# FIT_TCM_Main_PLL.net
KiCad netlist of a schematic drawn in Altium Designer
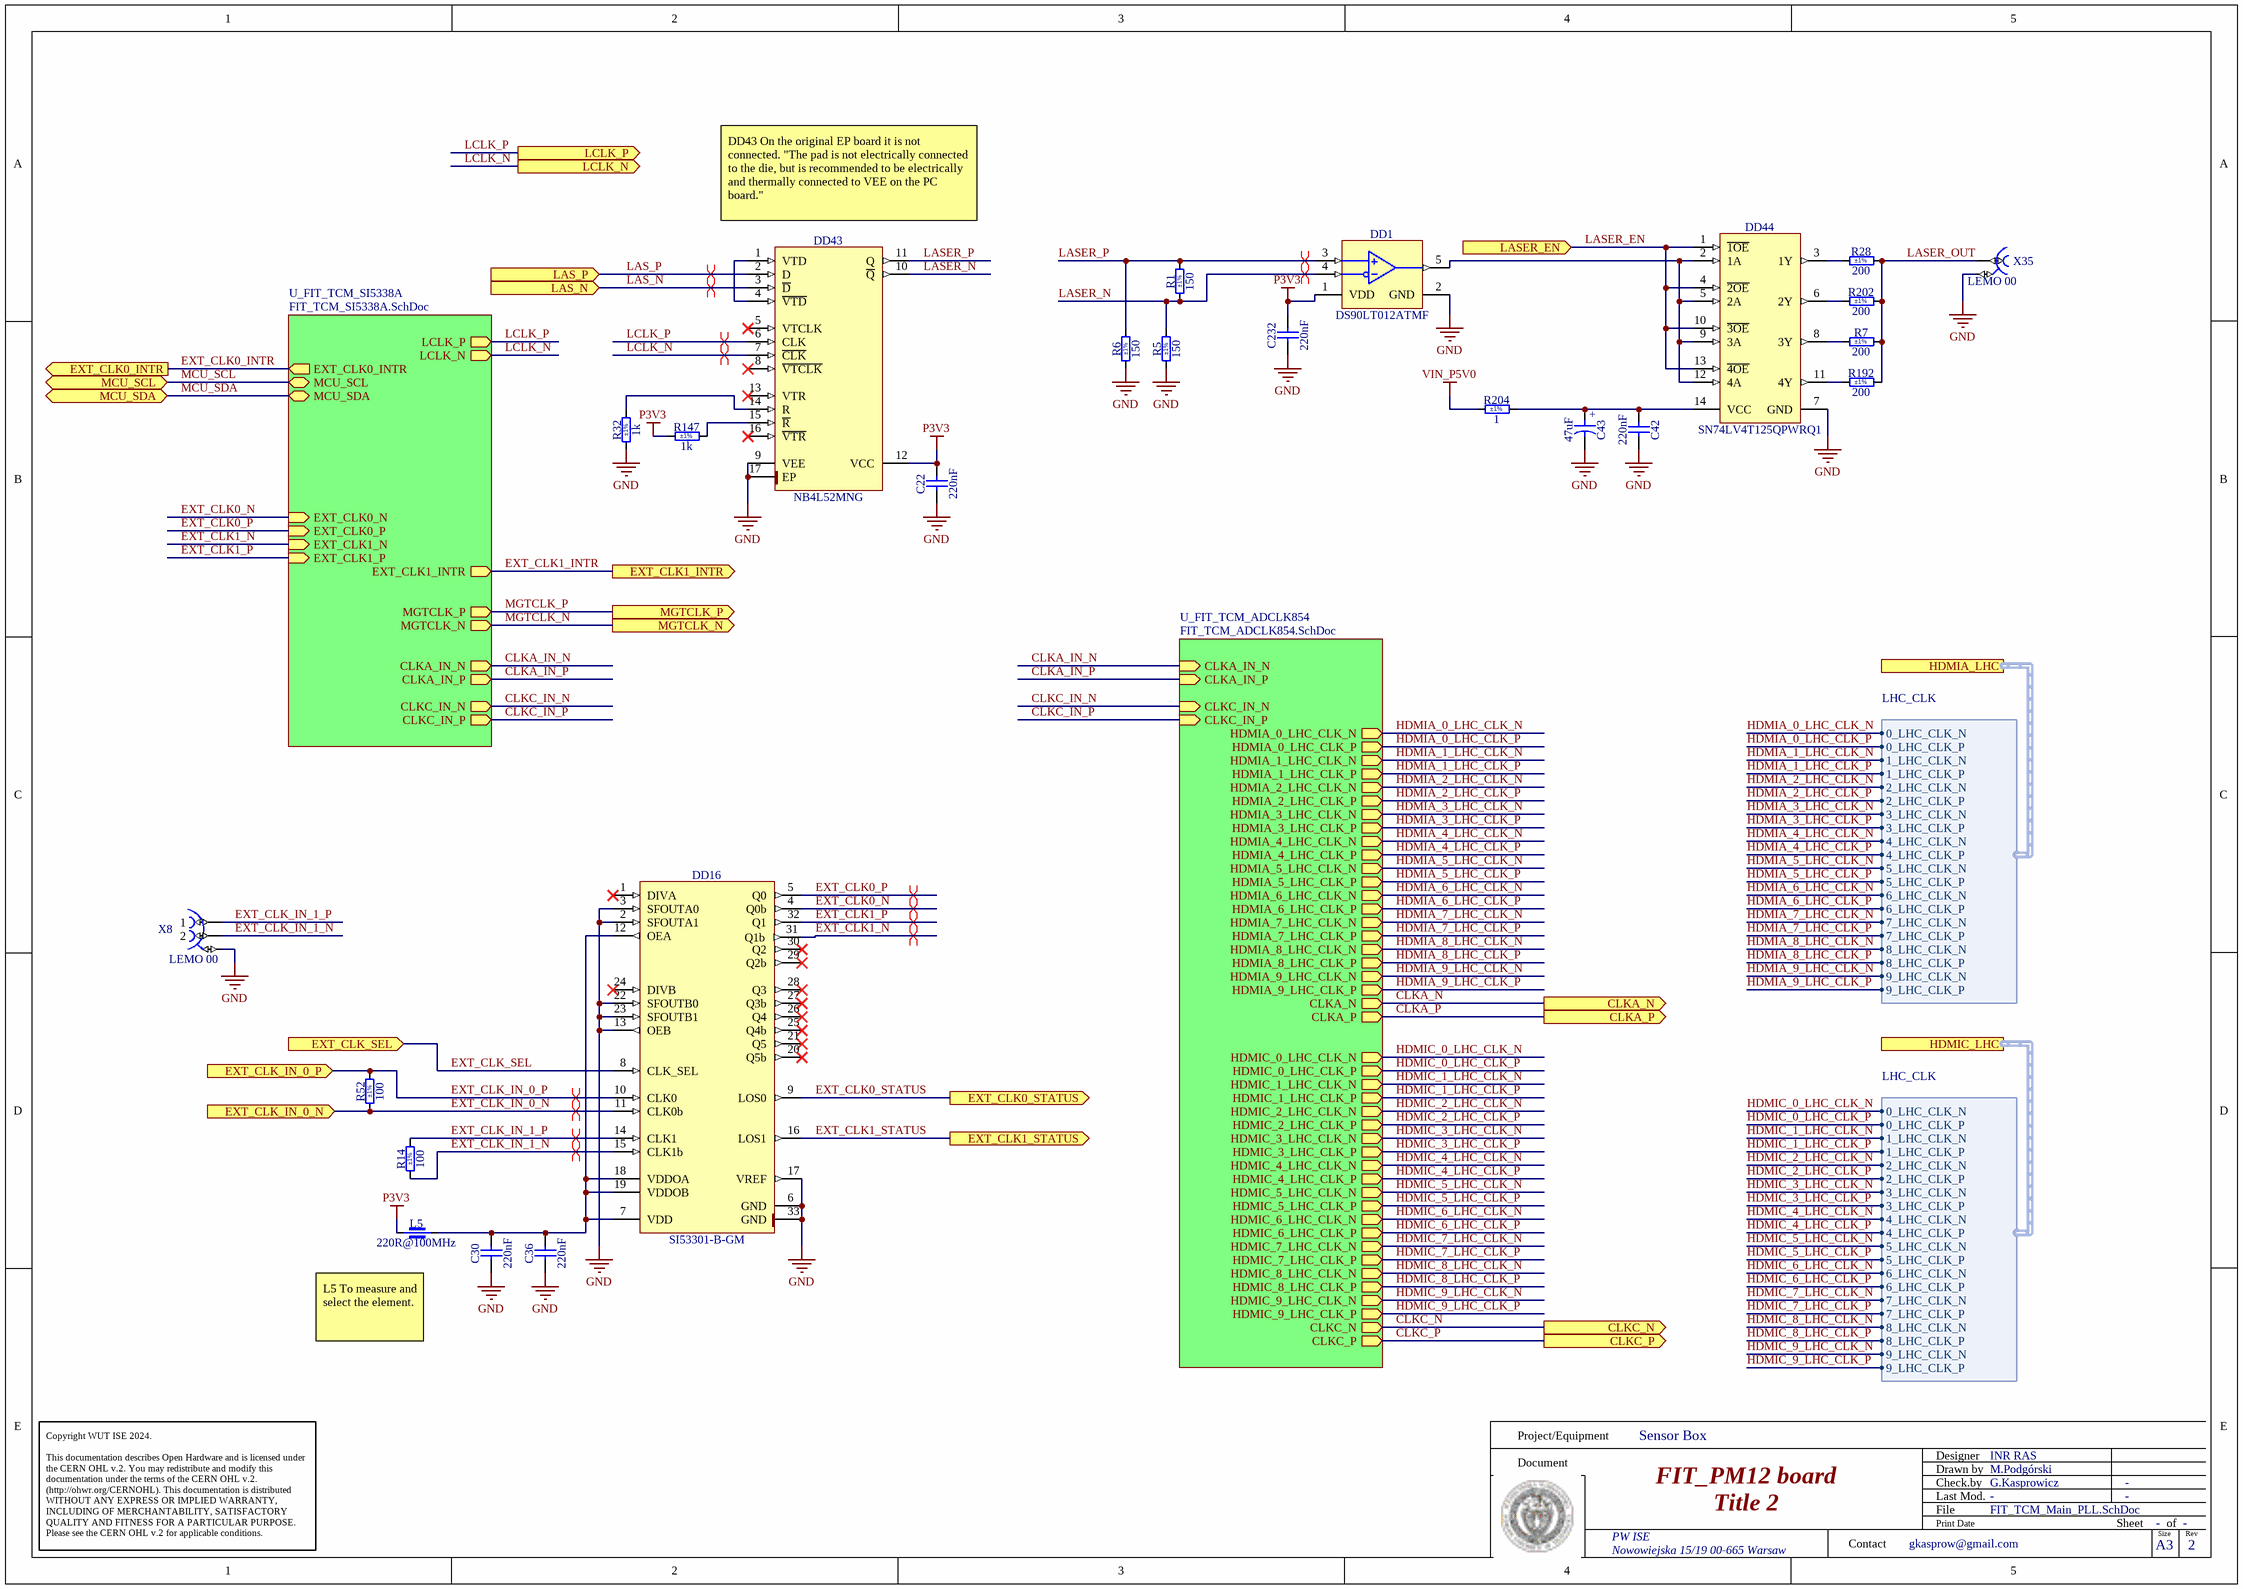
[diagram p0: FIT_TCM_Main_PLL.SchDoc]

(export (version "E")
  (design (tool "Eeschema 10.0.6"))
  (components
    (comp (ref "C22")
      (value "220nF")
      (footprint "CAPC2012X135N")
      (description "Non-polarised capacitor")
      (fields
        (field (name "PART NUMBER") "CC0805_220NF_50V_10%_X7R")
        (field (name "VOLTAGE") "50V")
        (field (name "AUTHOR") "CERN DEM JLC")
      )
      (libsource (lib "Capacitors") (part "Capacitor - non polarized"))
    )
    (comp (ref "C30")
      (value "220nF")
      (footprint "CAPC2012X135N")
      (description "Non-polarised capacitor")
      (fields
        (field (name "PART NUMBER") "CC0805_220NF_50V_10%_X7R")
        (field (name "VOLTAGE") "50V")
        (field (name "AUTHOR") "CERN DEM JLC")
      )
      (libsource (lib "Capacitors") (part "Capacitor - non polarized"))
    )
    (comp (ref "C36")
      (value "220nF")
      (footprint "CAPC2012X135N")
      (description "Non-polarised capacitor")
      (fields
        (field (name "PART NUMBER") "CC0805_220NF_50V_10%_X7R")
        (field (name "VOLTAGE") "50V")
        (field (name "AUTHOR") "CERN DEM JLC")
      )
      (libsource (lib "Capacitors") (part "Capacitor - non polarized"))
    )
    (comp (ref "C42")
      (value "220nF")
      (footprint "CAPC2012X135N")
      (description "Non-polarised capacitor")
      (fields
        (field (name "PART NUMBER") "CC0805_220NF_50V_10%_X7R")
        (field (name "VOLTAGE") "50V")
        (field (name "AUTHOR") "CERN DEM JLC")
      )
      (libsource (lib "Capacitors") (part "Capacitor - non polarized"))
    )
    (comp (ref "C43")
      (value "47uF")
      (footprint "CAPAE530X610N")
      (description "Polarised capacitor")
      (fields
        (field (name "PART NUMBER") "CAE530-610_47UF_16V_20%")
        (field (name "VOLTAGE") "16V")
        (field (name "AUTHOR") "CERN DEM HF")
      )
      (libsource (lib "Capacitors") (part "Capacitor - polarized"))
    )
    (comp (ref "C232")
      (value "220nF")
      (footprint "CAPC2012X135N")
      (description "Non-polarised capacitor")
      (fields
        (field (name "PART NUMBER") "CC0805_220NF_50V_10%_X7R")
        (field (name "VOLTAGE") "50V")
        (field (name "AUTHOR") "CERN DEM JLC")
      )
      (libsource (lib "Capacitors") (part "Capacitor - non polarized"))
    )
    (comp (ref "DD1")
      (value "DS90LT012ATMF")
      (footprint "SOT95P280X145-5N")
      (description "3V LVDS Single CMOS Differential Line Receiver")
      (fields (field (name "MANUFACTURER") "TEXAS INSTRUMENTS") (field (name "AUTHOR") "CERN DEM HF"))
      (libsource (lib "ICs And Semiconductors") (part "DS90LT012A"))
    )
    (comp (ref "DD16")
      (value "SI53301-B-GM")
      (footprint "QFN50P500X500X100-33N-S230")
      (description "I2C-Programmable Any-Frequency, Any-Output Quad Clock Generator")
      (fields (field (name "MANUFACTURER") "SKYWORKS") (field (name "AUTHOR") "CERN DEM HF"))
      (libsource (lib "ICs And Semiconductors") (part "SI53301"))
    )
    (comp (ref "DD43")
      (value "NB4L52MNG")
      (footprint "QFN50P300X300X100-17N-S185")
      (description "2.5 V/3.3 V/5.0 V Differential Data/Clock D Flip-Flop with Reset")
      (fields
        (field (name "MANUFACTURER") "ON SEMICONDUCTOR")
        (field (name "MANUFACTURER PART NUMBER") "NB4L52MN")
        (field (name "AUTHOR") "CERN DEM MR")
      )
      (libsource (lib "ICs And Semiconductors") (part "NB4L52MN"))
    )
    (comp (ref "DD44")
      (value "SN74LV4T125QPWRQ1")
      (footprint "SOP65P640X120-14N")
      (description "Quadruple Buffer Translator With 3-State Outputs")
      (fields (field (name "MANUFACTURER") "TEXAS INSTRUMENTS") (field (name "AUTHOR") "CERN DEM HF"))
      (libsource (lib "ICs And Semiconductors") (part "744T125"))
    )
    (comp (ref "L5")
      (value "220R@100MHz")
      (footprint "INDC2012X105N")
      (fields
        (field (name "PART NUMBER") "IND0805_TDK_MPZ2012S221A")
        (field (name "POWER") "3A")
        (field (name "TOLERANCE") "±25%")
        (field (name "AUTHOR") "CERN DEM HF")
      )
      (libsource (lib "Inductors & Transformers") (part "Ferrite Bead"))
    )
    (comp (ref "R1")
      (value "150")
      (footprint "RESC2012X60N")
      (description "Resistor - 1%")
      (fields
        (field (name "TOLERANCE") "±1%")
        (field (name "PART NUMBER") "R0805_150R_1%_0.125W_100PPM")
        (field (name "POWER") "0.125W")
        (field (name "AUTHOR") "CERN DEM JLC")
      )
      (libsource (lib "Resistors") (part "Resistor - 1%"))
    )
    (comp (ref "R5")
      (value "150")
      (footprint "RESC2012X60N")
      (description "Resistor - 1%")
      (fields
        (field (name "TOLERANCE") "±1%")
        (field (name "PART NUMBER") "R0805_150R_1%_0.125W_100PPM")
        (field (name "POWER") "0.125W")
        (field (name "AUTHOR") "CERN DEM JLC")
      )
      (libsource (lib "Resistors") (part "Resistor - 1%"))
    )
    (comp (ref "R6")
      (value "150")
      (footprint "RESC2012X60N")
      (description "Resistor - 1%")
      (fields
        (field (name "TOLERANCE") "±1%")
        (field (name "PART NUMBER") "R0805_150R_1%_0.125W_100PPM")
        (field (name "POWER") "0.125W")
        (field (name "AUTHOR") "CERN DEM JLC")
      )
      (libsource (lib "Resistors") (part "Resistor - 1%"))
    )
    (comp (ref "R7")
      (value "200")
      (footprint "RESC2012X60N")
      (description "Resistor - 1%")
      (fields
        (field (name "TOLERANCE") "±1%")
        (field (name "PART NUMBER") "R0805_200R_1%_0.125W_100PPM")
        (field (name "POWER") "0.125W")
        (field (name "AUTHOR") "CERN DEM JLC")
      )
      (libsource (lib "Resistors") (part "Resistor - 1%"))
    )
    (comp (ref "R14")
      (value "100")
      (footprint "RESC1608X55N")
      (description "Resistor - 1%")
      (fields
        (field (name "TOLERANCE") "±1%")
        (field (name "PART NUMBER") "R0603_100R_1%_0.1W_100PPM")
        (field (name "POWER") "0.1W")
        (field (name "AUTHOR") "CERN DEM JLC")
      )
      (libsource (lib "Resistors") (part "Resistor - 1%"))
    )
    (comp (ref "R28")
      (value "200")
      (footprint "RESC2012X60N")
      (description "Resistor - 1%")
      (fields
        (field (name "TOLERANCE") "±1%")
        (field (name "PART NUMBER") "R0805_200R_1%_0.125W_100PPM")
        (field (name "POWER") "0.125W")
        (field (name "AUTHOR") "CERN DEM JLC")
      )
      (libsource (lib "Resistors") (part "Resistor - 1%"))
    )
    (comp (ref "R32")
      (value "1k")
      (footprint "RESC2012X60N")
      (description "Resistor - 1%")
      (fields
        (field (name "TOLERANCE") "±1%")
        (field (name "PART NUMBER") "R0805_1K_1%_0.125W_100PPM")
        (field (name "POWER") "0.125W")
        (field (name "AUTHOR") "CERN DEM JLC")
      )
      (libsource (lib "Resistors") (part "Resistor - 1%"))
    )
    (comp (ref "R52")
      (value "100")
      (footprint "RESC1608X55N")
      (description "Resistor - 1%")
      (fields
        (field (name "TOLERANCE") "±1%")
        (field (name "PART NUMBER") "R0603_100R_1%_0.1W_100PPM")
        (field (name "POWER") "0.1W")
        (field (name "AUTHOR") "CERN DEM JLC")
      )
      (libsource (lib "Resistors") (part "Resistor - 1%"))
    )
    (comp (ref "R147")
      (value "1k")
      (footprint "RESC2012X60N")
      (description "Resistor - 1%")
      (fields
        (field (name "TOLERANCE") "±1%")
        (field (name "PART NUMBER") "R0805_1K_1%_0.125W_100PPM")
        (field (name "POWER") "0.125W")
        (field (name "AUTHOR") "CERN DEM JLC")
      )
      (libsource (lib "Resistors") (part "Resistor - 1%"))
    )
    (comp (ref "R192")
      (value "200")
      (footprint "RESC2012X60N")
      (description "Resistor - 1%")
      (fields
        (field (name "TOLERANCE") "±1%")
        (field (name "PART NUMBER") "R0805_200R_1%_0.125W_100PPM")
        (field (name "POWER") "0.125W")
        (field (name "AUTHOR") "CERN DEM JLC")
      )
      (libsource (lib "Resistors") (part "Resistor - 1%"))
    )
    (comp (ref "R202")
      (value "200")
      (footprint "RESC2012X60N")
      (description "Resistor - 1%")
      (fields
        (field (name "TOLERANCE") "±1%")
        (field (name "PART NUMBER") "R0805_200R_1%_0.125W_100PPM")
        (field (name "POWER") "0.125W")
        (field (name "AUTHOR") "CERN DEM JLC")
      )
      (libsource (lib "Resistors") (part "Resistor - 1%"))
    )
    (comp (ref "R204")
      (value "1")
      (footprint "RESC2012X60N")
      (description "Resistor - 1%")
      (fields
        (field (name "TOLERANCE") "±1%")
        (field (name "PART NUMBER") "R0805_1R_1%_0.125W_100PPM")
        (field (name "POWER") "0.125W")
        (field (name "AUTHOR") "CERN DEM HF")
      )
      (libsource (lib "Resistors") (part "Resistor - 1%"))
    )
    (comp (ref "X8")
      (value "LEMO 00")
      (footprint "LEMO_EPG.00.302.NLN")
      (fields
        (field (name "PART NUMBER") "LEMO_EPG.00.302.NLN")
        (field (name "MANUFACTURER") "LEMO")
        (field (name "MANUFACTURER PART NUMBER") "EPG.00.302.NLN")
        (field (name "AUTHOR") "CERN DEM JLC")
      )
      (libsource (lib "Connectors") (part "Coax_2Female_1Shield"))
    )
    (comp (ref "X35")
      (value "LEMO 00")
      (footprint "LEMO_EPL.00.250.NTN")
      (fields
        (field (name "PART NUMBER") "LEMO_EPL.00.250.NTN")
        (field (name "MANUFACTURER") "LEMO")
        (field (name "MANUFACTURER PART NUMBER") "EPL.00.250.NTN")
        (field (name "AUTHOR") "CERN DEM JLC")
      )
      (libsource (lib "Connectors") (part "Coax_1Female_1Shield"))
    )
  )
  (nets
    (net (code "11") (name "/EXT_CLK0_N") (class "Default")
      (node (ref "DD16") (pin "4") (pinfunction "Q0b_4") (pintype "output"))
    )
    (net (code "12") (name "/EXT_CLK0_P") (class "Default")
      (node (ref "DD16") (pin "5") (pinfunction "Q0_5") (pintype "output"))
    )
    (net (code "13") (name "/EXT_CLK0_STATUS") (class "Default")
      (node (ref "DD16") (pin "9") (pinfunction "LOS0_9") (pintype "output"))
    )
    (net (code "15") (name "/EXT_CLK1_N") (class "Default")
      (node (ref "DD16") (pin "31") (pinfunction "Q1b_31") (pintype "output"))
    )
    (net (code "16") (name "/EXT_CLK1_P") (class "Default")
      (node (ref "DD16") (pin "32") (pinfunction "Q1_32") (pintype "output"))
    )
    (net (code "17") (name "/EXT_CLK1_STATUS") (class "Default")
      (node (ref "DD16") (pin "16") (pinfunction "LOS1_16") (pintype "output"))
    )
    (net (code "18") (name "/EXT_CLK_IN_0_N") (class "Default")
      (node (ref "DD16") (pin "11") (pinfunction "CLK0b_11") (pintype "input"))
      (node (ref "R52") (pin "1") (pinfunction "1_1") (pintype "passive"))
    )
    (net (code "19") (name "/EXT_CLK_IN_0_P") (class "Default")
      (node (ref "DD16") (pin "10") (pinfunction "CLK0_10") (pintype "input"))
      (node (ref "R52") (pin "2") (pinfunction "2_2") (pintype "passive"))
    )
    (net (code "20") (name "/EXT_CLK_IN_1_N") (class "Default")
      (node (ref "DD16") (pin "15") (pinfunction "CLK1b_15") (pintype "input"))
      (node (ref "R14") (pin "1") (pinfunction "1_1") (pintype "passive"))
      (node (ref "X8") (pin "2") (pinfunction "2_2") (pintype "bidirectional"))
    )
    (net (code "21") (name "/EXT_CLK_IN_1_P") (class "Default")
      (node (ref "DD16") (pin "14") (pinfunction "CLK1_14") (pintype "input"))
      (node (ref "R14") (pin "2") (pinfunction "2_2") (pintype "passive"))
      (node (ref "X8") (pin "1") (pinfunction "1_1") (pintype "bidirectional"))
    )
    (net (code "22") (name "/EXT_CLK_SEL") (class "Default")
      (node (ref "DD16") (pin "8") (pinfunction "CLK_SEL_8") (pintype "input"))
    )
    (net (code "63") (name "/LASER_EN") (class "Default")
      (node (ref "DD44") (pin "1") (pinfunction "~{1OE}_1") (pintype "input"))
      (node (ref "DD44") (pin "10") (pinfunction "~{3OE}_10") (pintype "input"))
      (node (ref "DD44") (pin "13") (pinfunction "~{4OE}_13") (pintype "input"))
      (node (ref "DD44") (pin "4") (pinfunction "~{2OE}_4") (pintype "input"))
    )
    (net (code "64") (name "/LASER_N") (class "Default")
      (node (ref "DD1") (pin "4") (pinfunction "IN-_4") (pintype "input"))
      (node (ref "DD43") (pin "10") (pinfunction "~{Q}_10") (pintype "output"))
      (node (ref "R1") (pin "1") (pinfunction "1_1") (pintype "passive"))
      (node (ref "R5") (pin "2") (pinfunction "2_2") (pintype "passive"))
    )
    (net (code "65") (name "/LASER_OUT") (class "Default")
      (node (ref "R192") (pin "2") (pinfunction "2_2") (pintype "passive"))
      (node (ref "R202") (pin "2") (pinfunction "2_2") (pintype "passive"))
      (node (ref "R28") (pin "2") (pinfunction "2_2") (pintype "passive"))
      (node (ref "R7") (pin "2") (pinfunction "2_2") (pintype "passive"))
      (node (ref "X35") (pin "1") (pinfunction "1_1") (pintype "bidirectional"))
    )
    (net (code "66") (name "/LASER_P") (class "Default")
      (node (ref "DD1") (pin "3") (pinfunction "IN+_3") (pintype "input"))
      (node (ref "DD43") (pin "11") (pinfunction "Q_11") (pintype "output"))
      (node (ref "R1") (pin "2") (pinfunction "2_2") (pintype "passive"))
      (node (ref "R6") (pin "2") (pinfunction "2_2") (pintype "passive"))
    )
    (net (code "67") (name "/LAS_N") (class "Default")
      (node (ref "DD43") (pin "3") (pinfunction "~{D}_3") (pintype "input"))
    )
    (net (code "68") (name "/LAS_P") (class "Default")
      (node (ref "DD43") (pin "2") (pinfunction "D_2") (pintype "input"))
    )
    (net (code "69") (name "/LCLK_N") (class "Default")
      (node (ref "DD43") (pin "7") (pinfunction "~{CLK}_7") (pintype "input"))
    )
    (net (code "70") (name "/LCLK_P") (class "Default")
      (node (ref "DD43") (pin "6") (pinfunction "CLK_6") (pintype "input"))
    )
    (net (code "76") (name "GND") (class "Default")
      (node (ref "C22") (pin "1") (pinfunction "1_1") (pintype "passive"))
      (node (ref "C232") (pin "1") (pinfunction "1_1") (pintype "passive"))
      (node (ref "C30") (pin "1") (pinfunction "1_1") (pintype "passive"))
      (node (ref "C36") (pin "1") (pinfunction "1_1") (pintype "passive"))
      (node (ref "C42") (pin "2") (pinfunction "2_2") (pintype "passive"))
      (node (ref "C43") (pin "2") (pinfunction "2_2") (pintype "passive"))
      (node (ref "DD1") (pin "2") (pinfunction "GND_2") (pintype "power_in"))
      (node (ref "DD16") (pin "13") (pinfunction "OEB_13") (pintype "output"))
      (node (ref "DD16") (pin "17") (pinfunction "VREF_17") (pintype "output"))
      (node (ref "DD16") (pin "2") (pinfunction "SFOUTA1_2") (pintype "input"))
      (node (ref "DD16") (pin "22") (pinfunction "SFOUTB0_22") (pintype "input"))
      (node (ref "DD16") (pin "23") (pinfunction "SFOUTB1_23") (pintype "input"))
      (node (ref "DD16") (pin "3") (pinfunction "SFOUTA0_3") (pintype "input"))
      (node (ref "DD16") (pin "33") (pinfunction "GND_33") (pintype "power_in"))
      (node (ref "DD16") (pin "6") (pinfunction "GND_6") (pintype "power_in"))
      (node (ref "DD43") (pin "17") (pinfunction "EP_17") (pintype "power_in"))
      (node (ref "DD43") (pin "9") (pinfunction "VEE_9") (pintype "power_in"))
      (node (ref "DD44") (pin "7") (pinfunction "GND_7") (pintype "power_in"))
      (node (ref "R32") (pin "1") (pinfunction "1_1") (pintype "passive"))
      (node (ref "R5") (pin "1") (pinfunction "1_1") (pintype "passive"))
      (node (ref "R6") (pin "1") (pinfunction "1_1") (pintype "passive"))
      (node (ref "X35") (pin "2") (pinfunction "2_2") (pintype "bidirectional"))
      (node (ref "X8") (pin "3") (pinfunction "3_3") (pintype "bidirectional"))
    )
    (net (code "77") (name "Net-(DD1-TTLOUT)") (class "Default")
      (node (ref "DD1") (pin "5") (pinfunction "TTLOUT_5") (pintype "output"))
      (node (ref "DD44") (pin "12") (pinfunction "4A_12") (pintype "input"))
      (node (ref "DD44") (pin "2") (pinfunction "1A_2") (pintype "input"))
      (node (ref "DD44") (pin "5") (pinfunction "2A_5") (pintype "input"))
      (node (ref "DD44") (pin "9") (pinfunction "3A_9") (pintype "input"))
    )
    (net (code "78") (name "Net-(DD16-OEA)") (class "Default")
      (node (ref "C30") (pin "2") (pinfunction "2_2") (pintype "passive"))
      (node (ref "C36") (pin "2") (pinfunction "2_2") (pintype "passive"))
      (node (ref "DD16") (pin "12") (pinfunction "OEA_12") (pintype "output"))
      (node (ref "DD16") (pin "18") (pinfunction "VDDOA_18") (pintype "power_in"))
      (node (ref "DD16") (pin "19") (pinfunction "VDDOB_19") (pintype "power_in"))
      (node (ref "DD16") (pin "7") (pinfunction "VDD_7") (pintype "power_in"))
      (node (ref "L5") (pin "2") (pinfunction "2_2") (pintype "passive"))
    )
    (net (code "79") (name "Net-(DD43-R)") (class "Default")
      (node (ref "DD43") (pin "14") (pinfunction "R_14") (pintype "input"))
      (node (ref "R32") (pin "2") (pinfunction "2_2") (pintype "passive"))
    )
    (net (code "80") (name "Net-(DD43-VTD)") (class "Default")
      (node (ref "DD43") (pin "1") (pinfunction "VTD_1") (pintype "input"))
      (node (ref "DD43") (pin "4") (pinfunction "~{VTD}_4") (pintype "input"))
    )
    (net (code "81") (name "Net-(DD43-~{R})") (class "Default")
      (node (ref "DD43") (pin "15") (pinfunction "~{R}_15") (pintype "input"))
      (node (ref "R147") (pin "2") (pinfunction "2_2") (pintype "passive"))
    )
    (net (code "82") (name "Net-(DD44-1Y)") (class "Default")
      (node (ref "DD44") (pin "3") (pinfunction "1Y_3") (pintype "output"))
      (node (ref "R28") (pin "1") (pinfunction "1_1") (pintype "passive"))
    )
    (net (code "83") (name "Net-(DD44-2Y)") (class "Default")
      (node (ref "DD44") (pin "6") (pinfunction "2Y_6") (pintype "output"))
      (node (ref "R202") (pin "1") (pinfunction "1_1") (pintype "passive"))
    )
    (net (code "84") (name "Net-(DD44-3Y)") (class "Default")
      (node (ref "DD44") (pin "8") (pinfunction "3Y_8") (pintype "output"))
      (node (ref "R7") (pin "1") (pinfunction "1_1") (pintype "passive"))
    )
    (net (code "85") (name "Net-(DD44-4Y)") (class "Default")
      (node (ref "DD44") (pin "11") (pinfunction "4Y_11") (pintype "output"))
      (node (ref "R192") (pin "1") (pinfunction "1_1") (pintype "passive"))
    )
    (net (code "86") (name "Net-(DD44-VCC)") (class "Default")
      (node (ref "C42") (pin "1") (pinfunction "1_1") (pintype "passive"))
      (node (ref "C43") (pin "1") (pinfunction "1_1") (pintype "passive"))
      (node (ref "DD44") (pin "14") (pinfunction "VCC_14") (pintype "power_in"))
      (node (ref "R204") (pin "2") (pinfunction "2_2") (pintype "passive"))
    )
    (net (code "87") (name "P3V3") (class "Default")
      (node (ref "C22") (pin "2") (pinfunction "2_2") (pintype "passive"))
      (node (ref "C232") (pin "2") (pinfunction "2_2") (pintype "passive"))
      (node (ref "DD1") (pin "1") (pinfunction "VDD_1") (pintype "power_in"))
      (node (ref "DD43") (pin "12") (pinfunction "VCC_12") (pintype "power_in"))
      (node (ref "L5") (pin "1") (pinfunction "1_1") (pintype "passive"))
      (node (ref "R147") (pin "1") (pinfunction "1_1") (pintype "passive"))
    )
    (net (code "88") (name "VIN_P5V0") (class "Default")
      (node (ref "R204") (pin "1") (pinfunction "1_1") (pintype "passive"))
    )
    (net (code "89") (name "unconnected-(DD16-DIVA-Pad1)") (class "Default")
      (node (ref "DD16") (pin "1") (pinfunction "DIVA_1") (pintype "input+no_connect"))
    )
    (net (code "90") (name "unconnected-(DD16-DIVB-Pad24)") (class "Default")
      (node (ref "DD16") (pin "24") (pinfunction "DIVB_24") (pintype "input+no_connect"))
    )
    (net (code "91") (name "unconnected-(DD16-Q2-Pad30)") (class "Default")
      (node (ref "DD16") (pin "30") (pinfunction "Q2_30") (pintype "output+no_connect"))
    )
    (net (code "92") (name "unconnected-(DD16-Q2b-Pad29)") (class "Default")
      (node (ref "DD16") (pin "29") (pinfunction "Q2b_29") (pintype "output+no_connect"))
    )
    (net (code "93") (name "unconnected-(DD16-Q3-Pad28)") (class "Default")
      (node (ref "DD16") (pin "28") (pinfunction "Q3_28") (pintype "output+no_connect"))
    )
    (net (code "94") (name "unconnected-(DD16-Q3b-Pad27)") (class "Default")
      (node (ref "DD16") (pin "27") (pinfunction "Q3b_27") (pintype "output+no_connect"))
    )
    (net (code "95") (name "unconnected-(DD16-Q4-Pad26)") (class "Default")
      (node (ref "DD16") (pin "26") (pinfunction "Q4_26") (pintype "output+no_connect"))
    )
    (net (code "96") (name "unconnected-(DD16-Q4b-Pad25)") (class "Default")
      (node (ref "DD16") (pin "25") (pinfunction "Q4b_25") (pintype "output+no_connect"))
    )
    (net (code "97") (name "unconnected-(DD16-Q5-Pad21)") (class "Default")
      (node (ref "DD16") (pin "21") (pinfunction "Q5_21") (pintype "output+no_connect"))
    )
    (net (code "98") (name "unconnected-(DD16-Q5b-Pad20)") (class "Default")
      (node (ref "DD16") (pin "20") (pinfunction "Q5b_20") (pintype "output+no_connect"))
    )
    (net (code "99") (name "unconnected-(DD43-VTCLK-Pad5)") (class "Default")
      (node (ref "DD43") (pin "5") (pinfunction "VTCLK_5") (pintype "input+no_connect"))
    )
    (net (code "100") (name "unconnected-(DD43-VTR-Pad13)") (class "Default")
      (node (ref "DD43") (pin "13") (pinfunction "VTR_13") (pintype "input+no_connect"))
    )
    (net (code "101") (name "unconnected-(DD43-~{VTCLK}-Pad8)") (class "Default")
      (node (ref "DD43") (pin "8") (pinfunction "~{VTCLK}_8") (pintype "input+no_connect"))
    )
    (net (code "102") (name "unconnected-(DD43-~{VTR}-Pad16)") (class "Default")
      (node (ref "DD43") (pin "16") (pinfunction "~{VTR}_16") (pintype "input+no_connect"))
    )
  )
)
